# esp32s_breakout.net
KiCad netlist of a schematic drawn in EAGLE
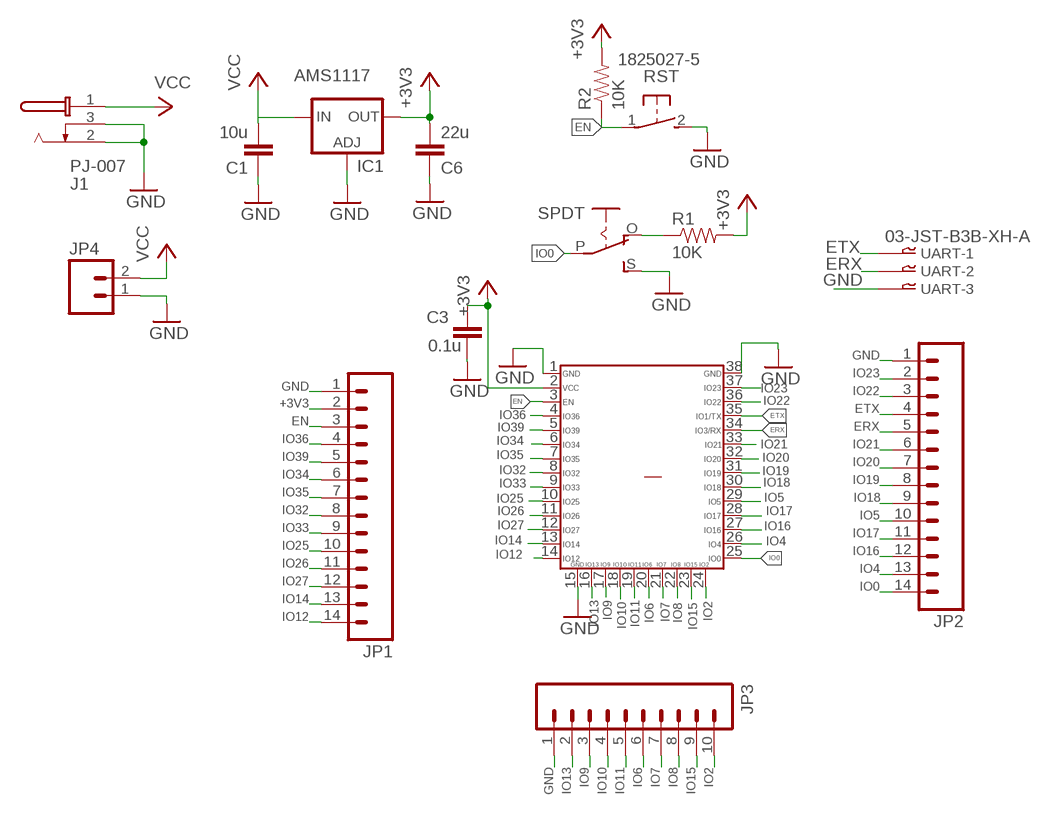
[diagram p0: schematic, sheet 1]

(export (version "E")
  (design (tool "Eeschema 10.0.6"))
  (components
    (comp (ref "C1")
      (value "10u")
      (footprint "eagle-import:0805-CAP-LARGEPADS")
      (libsource (lib "eagle-import") (part "CAP0805-CAP-LARGEPADS"))
    )
    (comp (ref "C3")
      (value "0.1u")
      (footprint "eagle-import:0805")
      (libsource (lib "eagle-import") (part "CAP0805"))
    )
    (comp (ref "C6")
      (value "22u")
      (footprint "eagle-import:0805")
      (libsource (lib "eagle-import") (part "CAP0805"))
    )
    (comp (ref "IC1")
      (value "AMS1117")
      (footprint "eagle-import:SOT223")
      (libsource (lib "eagle-import") (part "LD117A?S33TR"))
    )
    (comp (ref "J1")
      (value "PJ-007")
      (footprint "eagle-import:PJ-007")
      (libsource (lib "eagle-import") (part "PJ-007"))
    )
    (comp (ref "JP1")
      (value "M14")
      (footprint "eagle-import:1X14")
      (libsource (lib "eagle-import") (part "M14"))
    )
    (comp (ref "JP2")
      (value "M14")
      (footprint "eagle-import:1X14")
      (libsource (lib "eagle-import") (part "M14"))
    )
    (comp (ref "JP3")
      (value "M10SILK_FEMALE_PTH")
      (footprint "eagle-import:1X10")
      (libsource (lib "eagle-import") (part "M10SILK_FEMALE_PTH"))
    )
    (comp (ref "JP4")
      (value "M02PTH")
      (footprint "eagle-import:1X02")
      (libsource (lib "eagle-import") (part "M02PTH"))
    )
    (comp (ref "R1")
      (value "10K")
      (footprint "eagle-import:0805")
      (libsource (lib "eagle-import") (part "RESISTOR0805"))
    )
    (comp (ref "R2")
      (value "10K")
      (footprint "eagle-import:0805")
      (libsource (lib "eagle-import") (part "RESISTOR0805"))
    )
    (comp (ref "RST")
      (value "1825027-XBLK-152")
      (footprint "eagle-import:1825027-152")
      (libsource (lib "eagle-import") (part "1825027-XBLK-152"))
    )
    (comp (ref "SPDT")
      (value "EG1218S")
      (footprint "eagle-import:EG1218")
      (libsource (lib "eagle-import") (part "EG1218S"))
    )
    (comp (ref "U$1")
      (value "ESP32S32S")
      (footprint "eagle-import:ESP32")
      (libsource (lib "eagle-import") (part "ESP32S32S"))
    )
    (comp (ref "UART")
      (value "03-JST-B3B-XH-A")
      (footprint "eagle-import:B3B-XH")
      (libsource (lib "eagle-import") (part "03-JST-B3B-XH-A"))
    )
  )
  (nets
    (net (code "1") (name "+3V3") (class "Default")
      (node (ref "C3") (pin "1") (pinfunction "1_1") (pintype "passive"))
      (node (ref "C6") (pin "2") (pinfunction "2_2") (pintype "passive"))
      (node (ref "IC1") (pin "4") (pinfunction "OUT_4") (pintype "passive"))
      (node (ref "JP1") (pin "2") (pinfunction "2_2") (pintype "passive"))
      (node (ref "R1") (pin "2") (pinfunction "2_2") (pintype "passive"))
      (node (ref "R2") (pin "2") (pinfunction "2_2") (pintype "passive"))
      (node (ref "U$1") (pin "2") (pinfunction "P$2_2") (pintype "bidirectional"))
    )
    (net (code "2") (name "/IO2") (class "Default")
      (node (ref "JP3") (pin "10") (pinfunction "10_10") (pintype "passive"))
      (node (ref "U$1") (pin "24") (pinfunction "P$24_24") (pintype "bidirectional"))
    )
    (net (code "3") (name "/IO4") (class "Default")
      (node (ref "JP2") (pin "13") (pinfunction "13_13") (pintype "passive"))
      (node (ref "U$1") (pin "26") (pinfunction "P$26_26") (pintype "bidirectional"))
    )
    (net (code "4") (name "/IO5") (class "Default")
      (node (ref "JP2") (pin "10") (pinfunction "10_10") (pintype "passive"))
      (node (ref "U$1") (pin "29") (pinfunction "P$29_29") (pintype "bidirectional"))
    )
    (net (code "5") (name "/IO6") (class "Default")
      (node (ref "JP3") (pin "6") (pinfunction "6_6") (pintype "passive"))
      (node (ref "U$1") (pin "20") (pinfunction "P$20_20") (pintype "bidirectional"))
    )
    (net (code "6") (name "/IO7") (class "Default")
      (node (ref "JP3") (pin "7") (pinfunction "7_7") (pintype "passive"))
      (node (ref "U$1") (pin "21") (pinfunction "P$21_21") (pintype "bidirectional"))
    )
    (net (code "7") (name "/IO8") (class "Default")
      (node (ref "JP3") (pin "8") (pinfunction "8_8") (pintype "passive"))
      (node (ref "U$1") (pin "22") (pinfunction "P$22_22") (pintype "bidirectional"))
    )
    (net (code "8") (name "/IO9") (class "Default")
      (node (ref "JP3") (pin "3") (pinfunction "3_3") (pintype "passive"))
      (node (ref "U$1") (pin "17") (pinfunction "P$17_17") (pintype "bidirectional"))
    )
    (net (code "9") (name "/IO10") (class "Default")
      (node (ref "JP3") (pin "4") (pinfunction "4_4") (pintype "passive"))
      (node (ref "U$1") (pin "18") (pinfunction "P$18_18") (pintype "bidirectional"))
    )
    (net (code "10") (name "/IO11") (class "Default")
      (node (ref "JP3") (pin "5") (pinfunction "5_5") (pintype "passive"))
      (node (ref "U$1") (pin "19") (pinfunction "P$19_19") (pintype "bidirectional"))
    )
    (net (code "11") (name "/IO12") (class "Default")
      (node (ref "JP1") (pin "14") (pinfunction "14_14") (pintype "passive"))
      (node (ref "U$1") (pin "14") (pinfunction "P$14_14") (pintype "bidirectional"))
    )
    (net (code "12") (name "/IO13") (class "Default")
      (node (ref "JP3") (pin "2") (pinfunction "2_2") (pintype "passive"))
      (node (ref "U$1") (pin "16") (pinfunction "P$16_16") (pintype "bidirectional"))
    )
    (net (code "13") (name "/IO14") (class "Default")
      (node (ref "JP1") (pin "13") (pinfunction "13_13") (pintype "passive"))
      (node (ref "U$1") (pin "13") (pinfunction "P$13_13") (pintype "bidirectional"))
    )
    (net (code "14") (name "/IO15") (class "Default")
      (node (ref "JP3") (pin "9") (pinfunction "9_9") (pintype "passive"))
      (node (ref "U$1") (pin "23") (pinfunction "P$23_23") (pintype "bidirectional"))
    )
    (net (code "15") (name "/IO16") (class "Default")
      (node (ref "JP2") (pin "12") (pinfunction "12_12") (pintype "passive"))
      (node (ref "U$1") (pin "27") (pinfunction "P$27_27") (pintype "bidirectional"))
    )
    (net (code "16") (name "/IO17") (class "Default")
      (node (ref "JP2") (pin "11") (pinfunction "11_11") (pintype "passive"))
      (node (ref "U$1") (pin "28") (pinfunction "P$28_28") (pintype "bidirectional"))
    )
    (net (code "17") (name "/IO18") (class "Default")
      (node (ref "JP2") (pin "9") (pinfunction "9_9") (pintype "passive"))
      (node (ref "U$1") (pin "30") (pinfunction "P$30_30") (pintype "bidirectional"))
    )
    (net (code "18") (name "/IO19") (class "Default")
      (node (ref "JP2") (pin "8") (pinfunction "8_8") (pintype "passive"))
      (node (ref "U$1") (pin "31") (pinfunction "P$31_31") (pintype "bidirectional"))
    )
    (net (code "19") (name "/IO20") (class "Default")
      (node (ref "JP2") (pin "7") (pinfunction "7_7") (pintype "passive"))
      (node (ref "U$1") (pin "32") (pinfunction "P$32_32") (pintype "bidirectional"))
    )
    (net (code "20") (name "/IO21") (class "Default")
      (node (ref "JP2") (pin "6") (pinfunction "6_6") (pintype "passive"))
      (node (ref "U$1") (pin "33") (pinfunction "P$33_33") (pintype "bidirectional"))
    )
    (net (code "21") (name "/IO22") (class "Default")
      (node (ref "JP2") (pin "3") (pinfunction "3_3") (pintype "passive"))
      (node (ref "U$1") (pin "36") (pinfunction "P$36_36") (pintype "bidirectional"))
    )
    (net (code "22") (name "/IO23") (class "Default")
      (node (ref "JP2") (pin "2") (pinfunction "2_2") (pintype "passive"))
      (node (ref "U$1") (pin "37") (pinfunction "P$37_37") (pintype "bidirectional"))
    )
    (net (code "23") (name "/IO25") (class "Default")
      (node (ref "JP1") (pin "10") (pinfunction "10_10") (pintype "passive"))
      (node (ref "U$1") (pin "10") (pinfunction "P$10_10") (pintype "bidirectional"))
    )
    (net (code "24") (name "/IO26") (class "Default")
      (node (ref "JP1") (pin "11") (pinfunction "11_11") (pintype "passive"))
      (node (ref "U$1") (pin "11") (pinfunction "P$11_11") (pintype "bidirectional"))
    )
    (net (code "25") (name "/IO27") (class "Default")
      (node (ref "JP1") (pin "12") (pinfunction "12_12") (pintype "passive"))
      (node (ref "U$1") (pin "12") (pinfunction "P$12_12") (pintype "bidirectional"))
    )
    (net (code "26") (name "/IO32") (class "Default")
      (node (ref "JP1") (pin "8") (pinfunction "8_8") (pintype "passive"))
      (node (ref "U$1") (pin "8") (pinfunction "P$8_8") (pintype "bidirectional"))
    )
    (net (code "27") (name "/IO33") (class "Default")
      (node (ref "JP1") (pin "9") (pinfunction "9_9") (pintype "passive"))
      (node (ref "U$1") (pin "9") (pinfunction "P$9_9") (pintype "bidirectional"))
    )
    (net (code "28") (name "/IO34") (class "Default")
      (node (ref "JP1") (pin "6") (pinfunction "6_6") (pintype "passive"))
      (node (ref "U$1") (pin "6") (pinfunction "P$6_6") (pintype "bidirectional"))
    )
    (net (code "29") (name "/IO35") (class "Default")
      (node (ref "JP1") (pin "7") (pinfunction "7_7") (pintype "passive"))
      (node (ref "U$1") (pin "7") (pinfunction "P$7_7") (pintype "bidirectional"))
    )
    (net (code "30") (name "/IO36") (class "Default")
      (node (ref "JP1") (pin "4") (pinfunction "4_4") (pintype "passive"))
      (node (ref "U$1") (pin "4") (pinfunction "P$4_4") (pintype "bidirectional"))
    )
    (net (code "31") (name "/IO39") (class "Default")
      (node (ref "JP1") (pin "5") (pinfunction "5_5") (pintype "passive"))
      (node (ref "U$1") (pin "5") (pinfunction "P$5_5") (pintype "bidirectional"))
    )
    (net (code "32") (name "/P$39") (class "Default")
      (node (ref "U$1") (pin "GNDTHRM") (pinfunction "P$39_GNDTHRM") (pintype "power_in"))
    )
    (net (code "33") (name "EN") (class "Default")
      (node (ref "JP1") (pin "3") (pinfunction "3_3") (pintype "passive"))
      (node (ref "R2") (pin "1") (pinfunction "1_1") (pintype "passive"))
      (node (ref "RST") (pin "1") (pinfunction "P_1") (pintype "passive"))
      (node (ref "U$1") (pin "3") (pinfunction "P$3_3") (pintype "bidirectional"))
    )
    (net (code "34") (name "ERX") (class "Default")
      (node (ref "JP2") (pin "5") (pinfunction "5_5") (pintype "passive"))
      (node (ref "U$1") (pin "34") (pinfunction "P$34_34") (pintype "bidirectional"))
      (node (ref "UART") (pin "P$2") (pinfunction "1_P$2") (pintype "passive"))
    )
    (net (code "35") (name "ETX") (class "Default")
      (node (ref "JP2") (pin "4") (pinfunction "4_4") (pintype "passive"))
      (node (ref "U$1") (pin "35") (pinfunction "P$35_35") (pintype "bidirectional"))
      (node (ref "UART") (pin "P$1") (pinfunction "1_P$1") (pintype "passive"))
    )
    (net (code "36") (name "GND") (class "Default")
      (node (ref "C1") (pin "1") (pinfunction "1_1") (pintype "passive"))
      (node (ref "C3") (pin "2") (pinfunction "2_2") (pintype "passive"))
      (node (ref "C6") (pin "1") (pinfunction "1_1") (pintype "passive"))
      (node (ref "IC1") (pin "1") (pinfunction "ADJ_1") (pintype "input"))
      (node (ref "J1") (pin "2") (pinfunction "S_2") (pintype "passive"))
      (node (ref "J1") (pin "3") (pinfunction "SS_3") (pintype "passive"))
      (node (ref "JP1") (pin "1") (pinfunction "1_1") (pintype "passive"))
      (node (ref "JP2") (pin "1") (pinfunction "1_1") (pintype "passive"))
      (node (ref "JP3") (pin "1") (pinfunction "1_1") (pintype "passive"))
      (node (ref "JP4") (pin "1") (pinfunction "1_1") (pintype "passive"))
      (node (ref "RST") (pin "2") (pinfunction "S_2") (pintype "passive"))
      (node (ref "SPDT") (pin "S") (pinfunction "S_S") (pintype "passive"))
      (node (ref "U$1") (pin "1") (pinfunction "P$1_1") (pintype "bidirectional"))
      (node (ref "U$1") (pin "15") (pinfunction "P$15_15") (pintype "bidirectional"))
      (node (ref "U$1") (pin "38") (pinfunction "P$38_38") (pintype "bidirectional"))
      (node (ref "UART") (pin "P$3") (pinfunction "1_P$3") (pintype "passive"))
    )
    (net (code "37") (name "IO0") (class "Default")
      (node (ref "JP2") (pin "14") (pinfunction "14_14") (pintype "passive"))
      (node (ref "SPDT") (pin "P") (pinfunction "P_P") (pintype "passive"))
      (node (ref "U$1") (pin "25") (pinfunction "P$25_25") (pintype "bidirectional"))
    )
    (net (code "38") (name "Net-(R1-Pad1)") (class "Default")
      (node (ref "R1") (pin "1") (pinfunction "1_1") (pintype "passive"))
      (node (ref "SPDT") (pin "O") (pinfunction "O_O") (pintype "passive"))
    )
    (net (code "39") (name "VCC") (class "Default")
      (node (ref "C1") (pin "2") (pinfunction "2_2") (pintype "passive"))
      (node (ref "IC1") (pin "3") (pinfunction "IN_3") (pintype "input"))
      (node (ref "J1") (pin "1") (pinfunction "T_1") (pintype "passive"))
      (node (ref "JP4") (pin "2") (pinfunction "2_2") (pintype "passive"))
    )
  )
)
